# DIO_Sheet1.net
KiCad netlist of a schematic drawn in Altium Designer
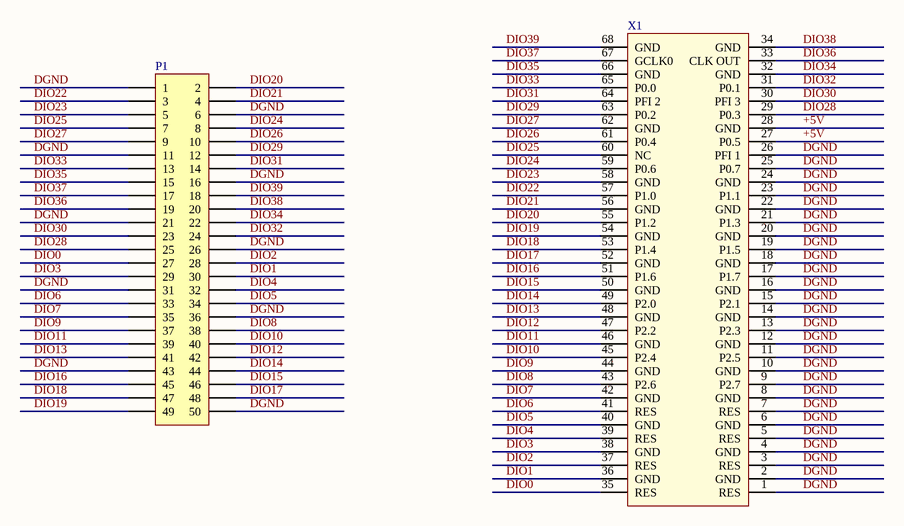
[diagram p0: DIO_Sheet1.SchDoc]

(export (version "E")
  (design (tool "Eeschema 10.0.6"))
  (components
    (comp (ref "P1")
      (value "Header 25X2")
      (footprint "HDR2X25")
      (description "Header, 25-Pin, Dual row")
      (fields (field (name "PUBLISHER") "Altium Limited"))
      (libsource (lib "Miscellaneous Connectors") (part "Header 25X2"))
    )
    (comp (ref "X1")
      (value "FPGA_Connector")
      (footprint "FPGA")
      (libsource (lib "Schlib") (part "FPGA_Connector"))
    )
  )
  (nets
    (net (code "1") (name "/+5V") (class "Default")
      (node (ref "X1") (pin "27") (pinfunction "P0.5_27") (pintype "passive"))
      (node (ref "X1") (pin "28") (pinfunction "GND_28") (pintype "passive"))
    )
    (net (code "2") (name "/DGND") (class "Default")
      (node (ref "P1") (pin "1") (pinfunction "1_1") (pintype "passive"))
      (node (ref "P1") (pin "11") (pinfunction "11_11") (pintype "passive"))
      (node (ref "P1") (pin "16") (pinfunction "16_16") (pintype "passive"))
      (node (ref "P1") (pin "21") (pinfunction "21_21") (pintype "passive"))
      (node (ref "P1") (pin "26") (pinfunction "26_26") (pintype "passive"))
      (node (ref "P1") (pin "31") (pinfunction "31_31") (pintype "passive"))
      (node (ref "P1") (pin "36") (pinfunction "36_36") (pintype "passive"))
      (node (ref "P1") (pin "43") (pinfunction "43_43") (pintype "passive"))
      (node (ref "P1") (pin "50") (pinfunction "50_50") (pintype "passive"))
      (node (ref "P1") (pin "6") (pinfunction "6_6") (pintype "passive"))
      (node (ref "X1") (pin "1") (pinfunction "RES_1") (pintype "passive"))
      (node (ref "X1") (pin "10") (pinfunction "GND_10") (pintype "passive"))
      (node (ref "X1") (pin "11") (pinfunction "P2.5_11") (pintype "passive"))
      (node (ref "X1") (pin "12") (pinfunction "GND_12") (pintype "passive"))
      (node (ref "X1") (pin "13") (pinfunction "P2.3_13") (pintype "passive"))
      (node (ref "X1") (pin "14") (pinfunction "GND_14") (pintype "passive"))
      (node (ref "X1") (pin "15") (pinfunction "P2.1_15") (pintype "passive"))
      (node (ref "X1") (pin "16") (pinfunction "GND_16") (pintype "passive"))
      (node (ref "X1") (pin "17") (pinfunction "P1.7_17") (pintype "passive"))
      (node (ref "X1") (pin "18") (pinfunction "GND_18") (pintype "passive"))
      (node (ref "X1") (pin "19") (pinfunction "P1.5_19") (pintype "passive"))
      (node (ref "X1") (pin "2") (pinfunction "GND_2") (pintype "passive"))
      (node (ref "X1") (pin "20") (pinfunction "GND_20") (pintype "passive"))
      (node (ref "X1") (pin "21") (pinfunction "P1.3_21") (pintype "passive"))
      (node (ref "X1") (pin "22") (pinfunction "GND_22") (pintype "passive"))
      (node (ref "X1") (pin "23") (pinfunction "P1.1_23") (pintype "passive"))
      (node (ref "X1") (pin "24") (pinfunction "GND_24") (pintype "passive"))
      (node (ref "X1") (pin "25") (pinfunction "P0.7_25") (pintype "passive"))
      (node (ref "X1") (pin "26") (pinfunction "PFI_1_26") (pintype "passive"))
      (node (ref "X1") (pin "3") (pinfunction "RES_3") (pintype "passive"))
      (node (ref "X1") (pin "4") (pinfunction "GND_4") (pintype "passive"))
      (node (ref "X1") (pin "5") (pinfunction "RES_5") (pintype "passive"))
      (node (ref "X1") (pin "6") (pinfunction "GND_6") (pintype "passive"))
      (node (ref "X1") (pin "7") (pinfunction "RES_7") (pintype "passive"))
      (node (ref "X1") (pin "8") (pinfunction "GND_8") (pintype "passive"))
      (node (ref "X1") (pin "9") (pinfunction "P2.7_9") (pintype "passive"))
    )
    (net (code "3") (name "/DIO0") (class "Default")
      (node (ref "P1") (pin "27") (pinfunction "27_27") (pintype "passive"))
      (node (ref "X1") (pin "35") (pinfunction "RES_35") (pintype "passive"))
    )
    (net (code "4") (name "/DIO1") (class "Default")
      (node (ref "P1") (pin "30") (pinfunction "30_30") (pintype "passive"))
      (node (ref "X1") (pin "36") (pinfunction "GND_36") (pintype "passive"))
    )
    (net (code "5") (name "/DIO2") (class "Default")
      (node (ref "P1") (pin "28") (pinfunction "28_28") (pintype "passive"))
      (node (ref "X1") (pin "37") (pinfunction "RES_37") (pintype "passive"))
    )
    (net (code "6") (name "/DIO3") (class "Default")
      (node (ref "P1") (pin "29") (pinfunction "29_29") (pintype "passive"))
      (node (ref "X1") (pin "38") (pinfunction "GND_38") (pintype "passive"))
    )
    (net (code "7") (name "/DIO4") (class "Default")
      (node (ref "P1") (pin "32") (pinfunction "32_32") (pintype "passive"))
      (node (ref "X1") (pin "39") (pinfunction "RES_39") (pintype "passive"))
    )
    (net (code "8") (name "/DIO5") (class "Default")
      (node (ref "P1") (pin "34") (pinfunction "34_34") (pintype "passive"))
      (node (ref "X1") (pin "40") (pinfunction "GND_40") (pintype "passive"))
    )
    (net (code "9") (name "/DIO6") (class "Default")
      (node (ref "P1") (pin "33") (pinfunction "33_33") (pintype "passive"))
      (node (ref "X1") (pin "41") (pinfunction "RES_41") (pintype "passive"))
    )
    (net (code "10") (name "/DIO7") (class "Default")
      (node (ref "P1") (pin "35") (pinfunction "35_35") (pintype "passive"))
      (node (ref "X1") (pin "42") (pinfunction "GND_42") (pintype "passive"))
    )
    (net (code "11") (name "/DIO8") (class "Default")
      (node (ref "P1") (pin "38") (pinfunction "38_38") (pintype "passive"))
      (node (ref "X1") (pin "43") (pinfunction "P2.6_43") (pintype "passive"))
    )
    (net (code "12") (name "/DIO9") (class "Default")
      (node (ref "P1") (pin "37") (pinfunction "37_37") (pintype "passive"))
      (node (ref "X1") (pin "44") (pinfunction "GND_44") (pintype "passive"))
    )
    (net (code "13") (name "/DIO10") (class "Default")
      (node (ref "P1") (pin "40") (pinfunction "40_40") (pintype "passive"))
      (node (ref "X1") (pin "45") (pinfunction "P2.4_45") (pintype "passive"))
    )
    (net (code "14") (name "/DIO11") (class "Default")
      (node (ref "P1") (pin "39") (pinfunction "39_39") (pintype "passive"))
      (node (ref "X1") (pin "46") (pinfunction "GND_46") (pintype "passive"))
    )
    (net (code "15") (name "/DIO12") (class "Default")
      (node (ref "P1") (pin "42") (pinfunction "42_42") (pintype "passive"))
      (node (ref "X1") (pin "47") (pinfunction "P2.2_47") (pintype "passive"))
    )
    (net (code "16") (name "/DIO13") (class "Default")
      (node (ref "P1") (pin "41") (pinfunction "41_41") (pintype "passive"))
      (node (ref "X1") (pin "48") (pinfunction "GND_48") (pintype "passive"))
    )
    (net (code "17") (name "/DIO14") (class "Default")
      (node (ref "P1") (pin "44") (pinfunction "44_44") (pintype "passive"))
      (node (ref "X1") (pin "49") (pinfunction "P2.0_49") (pintype "passive"))
    )
    (net (code "18") (name "/DIO15") (class "Default")
      (node (ref "P1") (pin "46") (pinfunction "46_46") (pintype "passive"))
      (node (ref "X1") (pin "50") (pinfunction "GND_50") (pintype "passive"))
    )
    (net (code "19") (name "/DIO16") (class "Default")
      (node (ref "P1") (pin "45") (pinfunction "45_45") (pintype "passive"))
      (node (ref "X1") (pin "51") (pinfunction "P1.6_51") (pintype "passive"))
    )
    (net (code "20") (name "/DIO17") (class "Default")
      (node (ref "P1") (pin "48") (pinfunction "48_48") (pintype "passive"))
      (node (ref "X1") (pin "52") (pinfunction "GND_52") (pintype "passive"))
    )
    (net (code "21") (name "/DIO18") (class "Default")
      (node (ref "P1") (pin "47") (pinfunction "47_47") (pintype "passive"))
      (node (ref "X1") (pin "53") (pinfunction "P1.4_53") (pintype "passive"))
    )
    (net (code "22") (name "/DIO19") (class "Default")
      (node (ref "P1") (pin "49") (pinfunction "49_49") (pintype "passive"))
      (node (ref "X1") (pin "54") (pinfunction "GND_54") (pintype "passive"))
    )
    (net (code "23") (name "/DIO20") (class "Default")
      (node (ref "P1") (pin "2") (pinfunction "2_2") (pintype "passive"))
      (node (ref "X1") (pin "55") (pinfunction "P1.2_55") (pintype "passive"))
    )
    (net (code "24") (name "/DIO21") (class "Default")
      (node (ref "P1") (pin "4") (pinfunction "4_4") (pintype "passive"))
      (node (ref "X1") (pin "56") (pinfunction "GND_56") (pintype "passive"))
    )
    (net (code "25") (name "/DIO22") (class "Default")
      (node (ref "P1") (pin "3") (pinfunction "3_3") (pintype "passive"))
      (node (ref "X1") (pin "57") (pinfunction "P1.0_57") (pintype "passive"))
    )
    (net (code "26") (name "/DIO23") (class "Default")
      (node (ref "P1") (pin "5") (pinfunction "5_5") (pintype "passive"))
      (node (ref "X1") (pin "58") (pinfunction "GND_58") (pintype "passive"))
    )
    (net (code "27") (name "/DIO24") (class "Default")
      (node (ref "P1") (pin "8") (pinfunction "8_8") (pintype "passive"))
      (node (ref "X1") (pin "59") (pinfunction "P0.6_59") (pintype "passive"))
    )
    (net (code "28") (name "/DIO25") (class "Default")
      (node (ref "P1") (pin "7") (pinfunction "7_7") (pintype "passive"))
      (node (ref "X1") (pin "60") (pinfunction "NC_60") (pintype "passive"))
    )
    (net (code "29") (name "/DIO26") (class "Default")
      (node (ref "P1") (pin "10") (pinfunction "10_10") (pintype "passive"))
      (node (ref "X1") (pin "61") (pinfunction "P0.4_61") (pintype "passive"))
    )
    (net (code "30") (name "/DIO27") (class "Default")
      (node (ref "P1") (pin "9") (pinfunction "9_9") (pintype "passive"))
      (node (ref "X1") (pin "62") (pinfunction "GND_62") (pintype "passive"))
    )
    (net (code "31") (name "/DIO28") (class "Default")
      (node (ref "P1") (pin "25") (pinfunction "25_25") (pintype "passive"))
      (node (ref "X1") (pin "29") (pinfunction "P0.3_29") (pintype "passive"))
    )
    (net (code "32") (name "/DIO29") (class "Default")
      (node (ref "P1") (pin "12") (pinfunction "12_12") (pintype "passive"))
      (node (ref "X1") (pin "63") (pinfunction "P0.2_63") (pintype "passive"))
    )
    (net (code "33") (name "/DIO30") (class "Default")
      (node (ref "P1") (pin "23") (pinfunction "23_23") (pintype "passive"))
      (node (ref "X1") (pin "30") (pinfunction "PFI_3_30") (pintype "passive"))
    )
    (net (code "34") (name "/DIO31") (class "Default")
      (node (ref "P1") (pin "14") (pinfunction "14_14") (pintype "passive"))
      (node (ref "X1") (pin "64") (pinfunction "PFI_2_64") (pintype "passive"))
    )
    (net (code "35") (name "/DIO32") (class "Default")
      (node (ref "P1") (pin "24") (pinfunction "24_24") (pintype "passive"))
      (node (ref "X1") (pin "31") (pinfunction "P0.1_31") (pintype "passive"))
    )
    (net (code "36") (name "/DIO33") (class "Default")
      (node (ref "P1") (pin "13") (pinfunction "13_13") (pintype "passive"))
      (node (ref "X1") (pin "65") (pinfunction "P0.0_65") (pintype "passive"))
    )
    (net (code "37") (name "/DIO34") (class "Default")
      (node (ref "P1") (pin "22") (pinfunction "22_22") (pintype "passive"))
      (node (ref "X1") (pin "32") (pinfunction "GND_32") (pintype "passive"))
    )
    (net (code "38") (name "/DIO35") (class "Default")
      (node (ref "P1") (pin "15") (pinfunction "15_15") (pintype "passive"))
      (node (ref "X1") (pin "66") (pinfunction "GND_66") (pintype "passive"))
    )
    (net (code "39") (name "/DIO36") (class "Default")
      (node (ref "P1") (pin "19") (pinfunction "19_19") (pintype "passive"))
      (node (ref "X1") (pin "33") (pinfunction "CLK_OUT_33") (pintype "passive"))
    )
    (net (code "40") (name "/DIO37") (class "Default")
      (node (ref "P1") (pin "17") (pinfunction "17_17") (pintype "passive"))
      (node (ref "X1") (pin "67") (pinfunction "GCLK0_67") (pintype "passive"))
    )
    (net (code "41") (name "/DIO38") (class "Default")
      (node (ref "P1") (pin "20") (pinfunction "20_20") (pintype "passive"))
      (node (ref "X1") (pin "34") (pinfunction "GND_34") (pintype "passive"))
    )
    (net (code "42") (name "/DIO39") (class "Default")
      (node (ref "P1") (pin "18") (pinfunction "18_18") (pintype "passive"))
      (node (ref "X1") (pin "68") (pinfunction "GND_68") (pintype "passive"))
    )
  )
)
